# Pure_Keys_aec-pcb4-inprogress.net
KiCad netlist of a schematic drawn in EAGLE
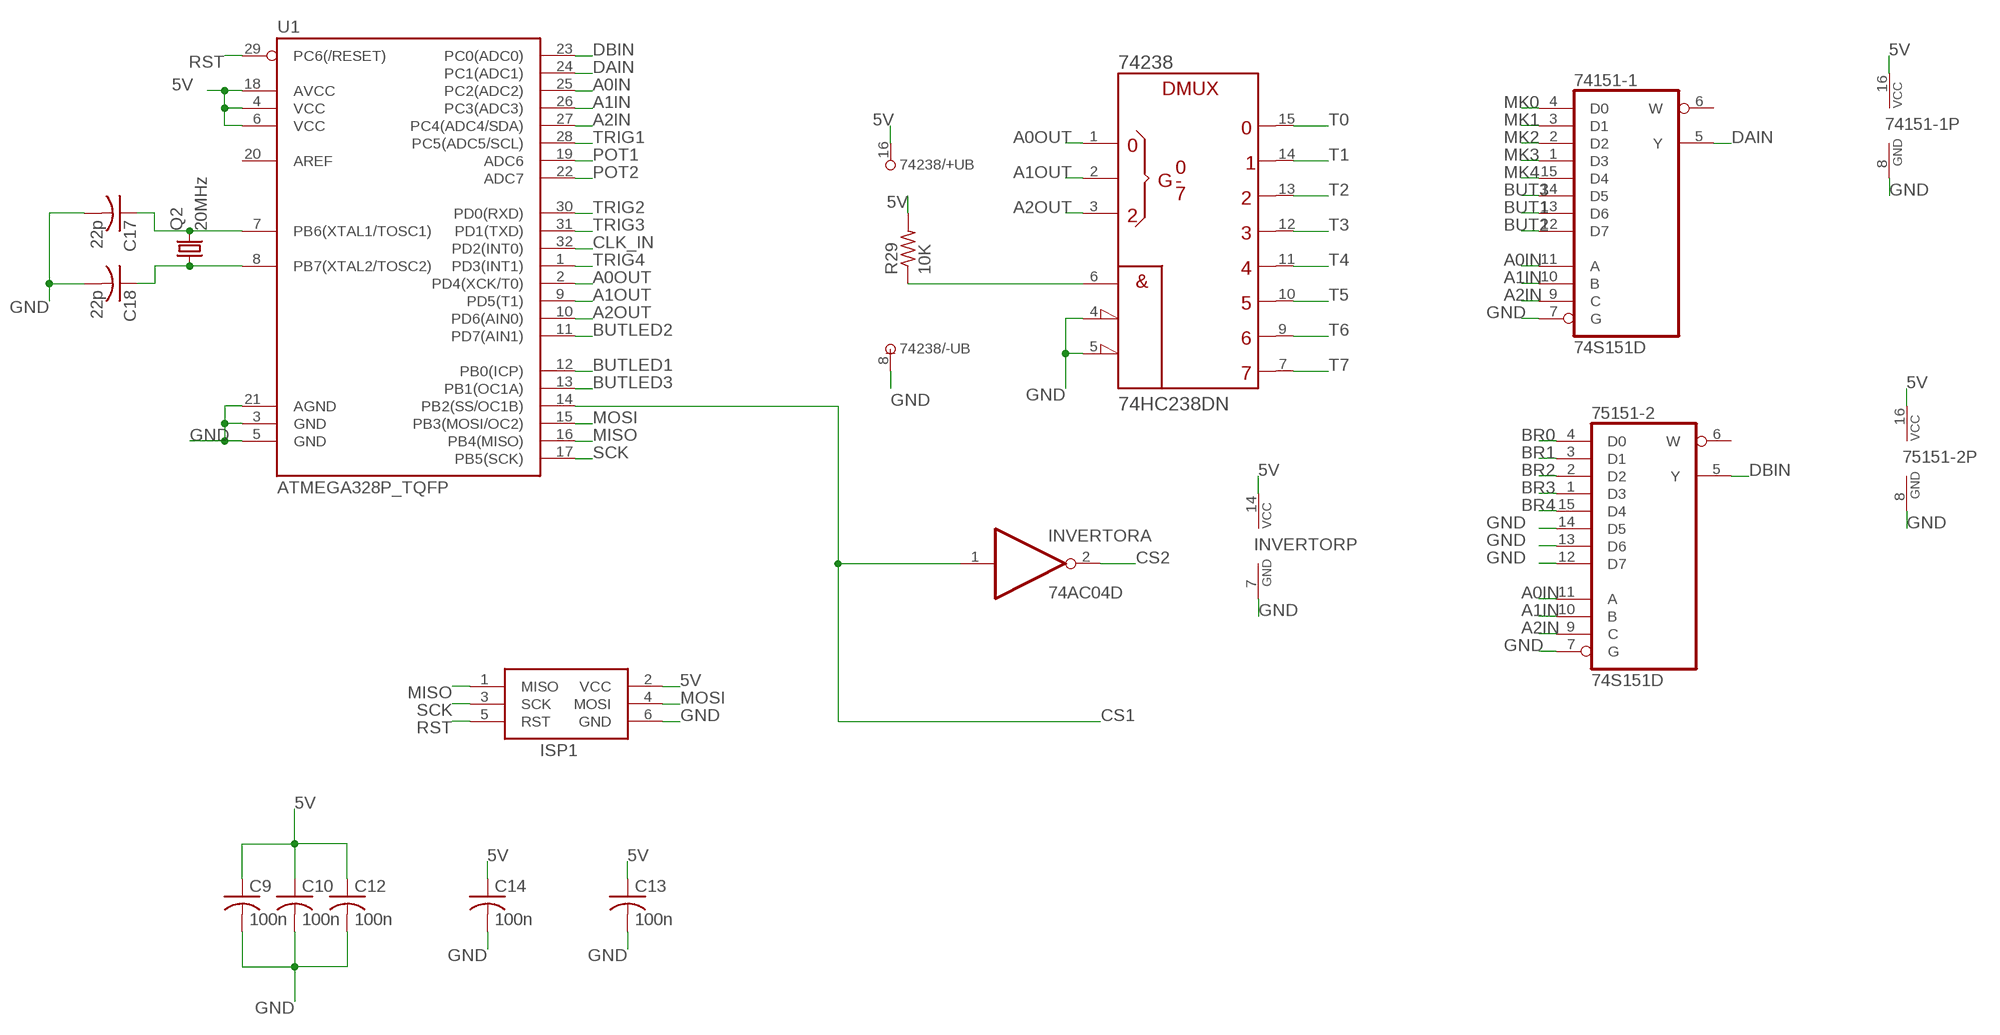
[diagram p0: schematic, sheet 1]
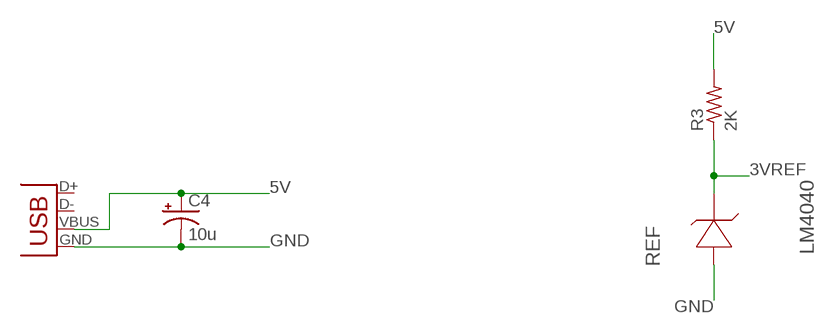
[diagram p1: schematic, sheet 2]
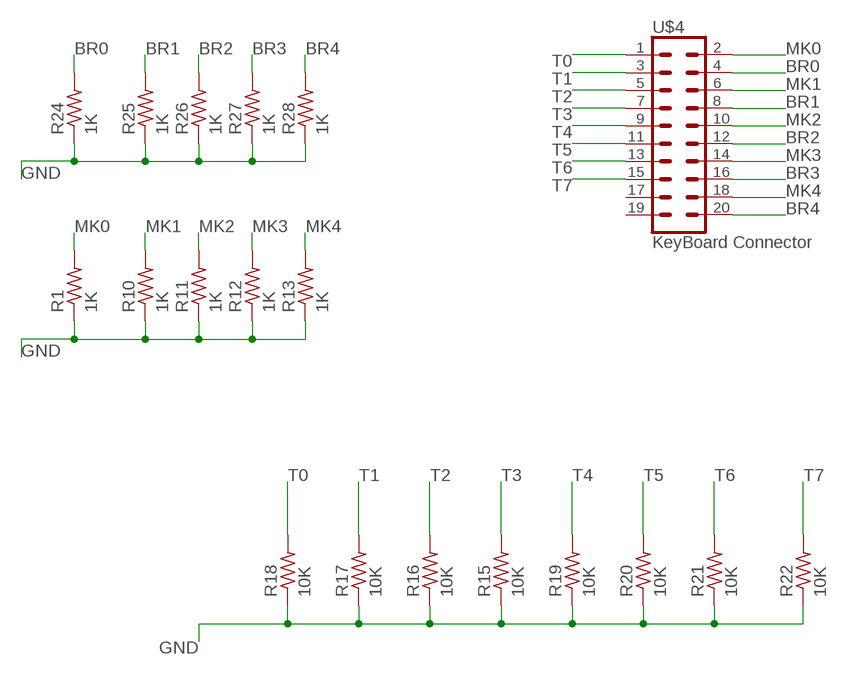
[diagram p2: schematic, sheet 3]
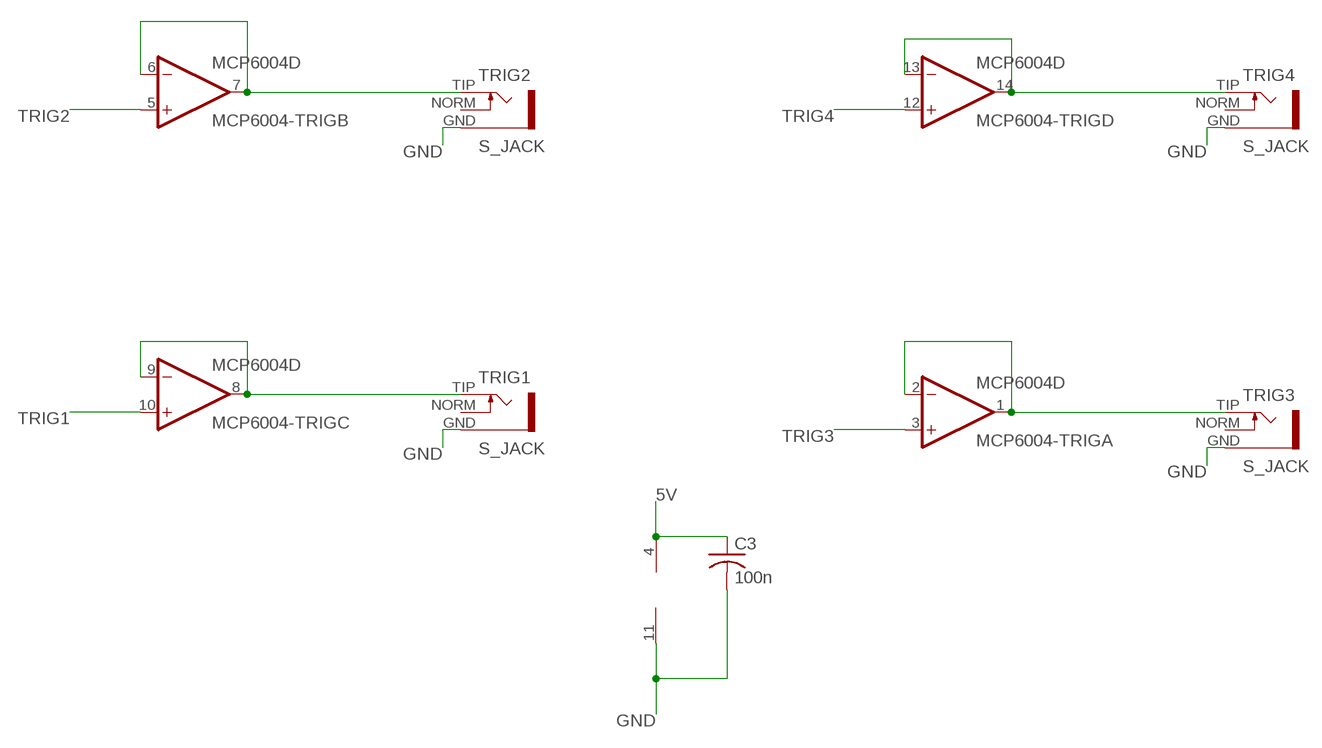
[diagram p3: schematic, sheet 4]
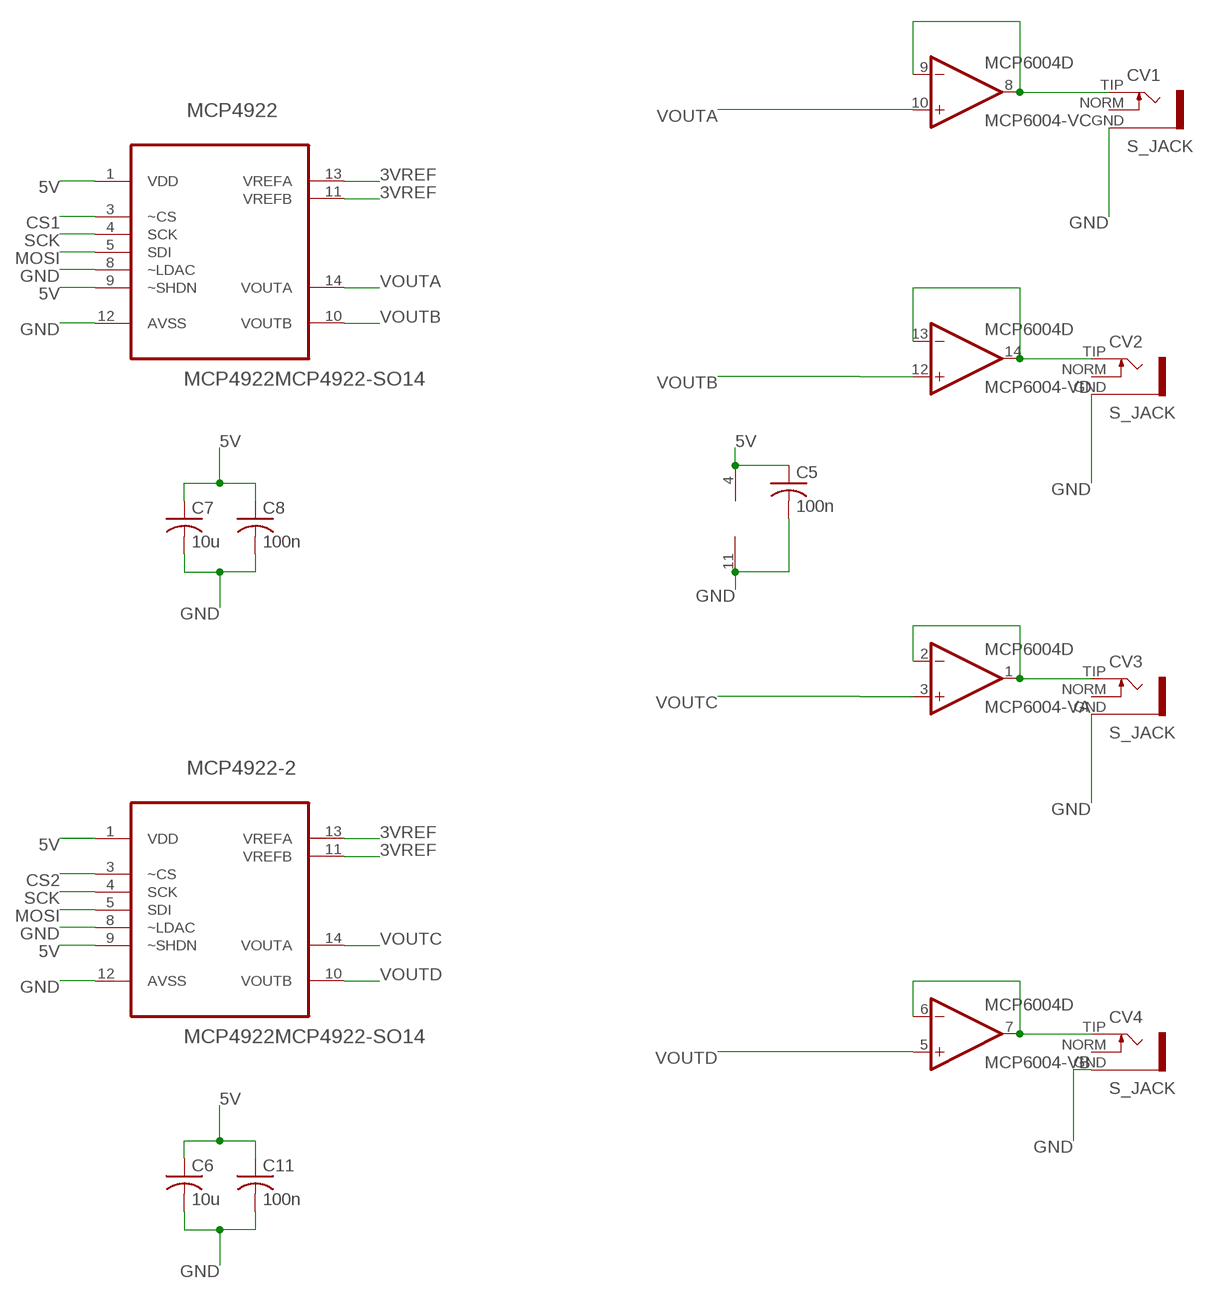
[diagram p4: schematic, sheet 5]
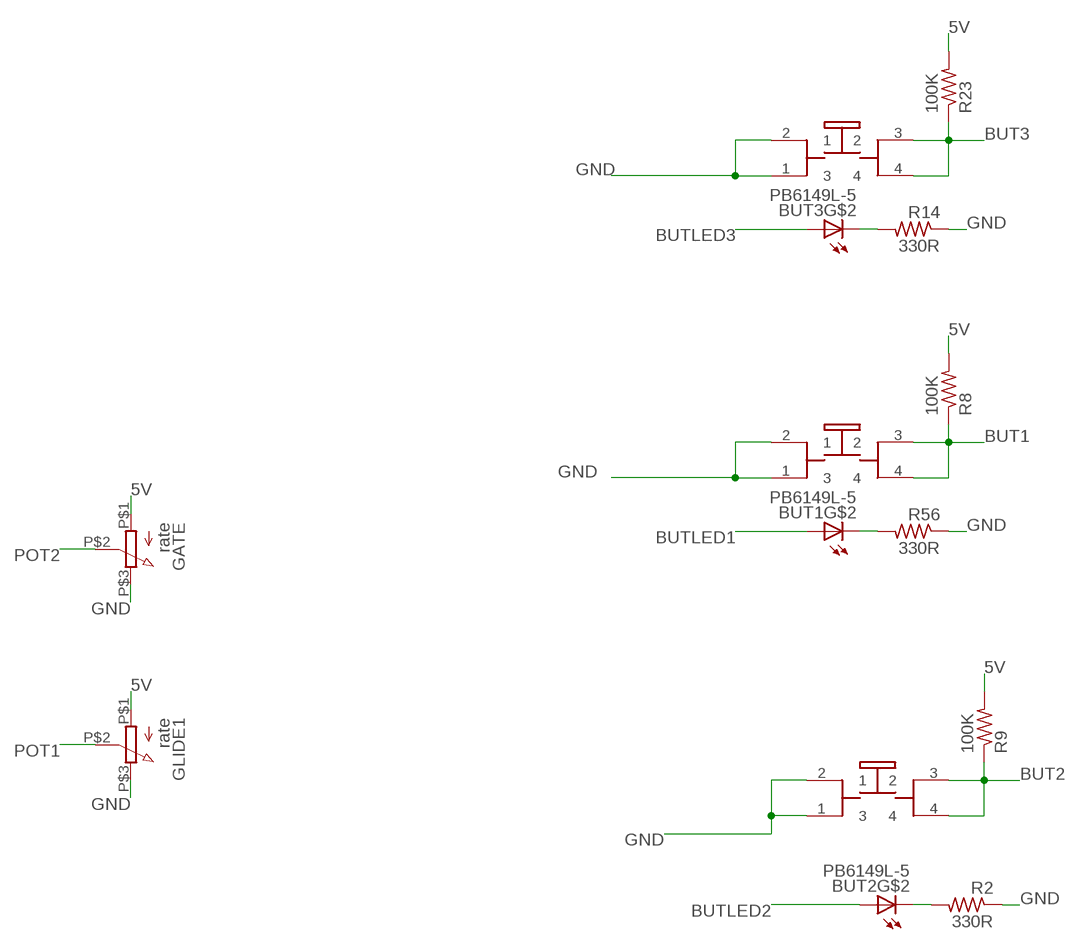
[diagram p5: schematic, sheet 6]
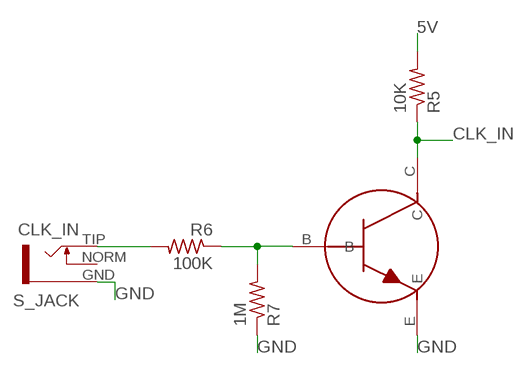
[diagram p6: schematic, sheet 7]

(export (version "E")
  (design (tool "Eeschema 10.0.6"))
  (components
    (comp (ref "CLK_IN")
      (value "S_JACK")
      (footprint "eagle-import:S_JACK")
      (libsource (lib "eagle-import") (part "S_JACK"))
    )
    (comp (ref "CLOCK")
      (value "2N3904")
      (footprint "eagle-import:TRANSISTOR_SINGLE_N-TYPE")
      (fields (field (name "RS-PART") "725-8616 "))
      (libsource (lib "eagle-import") (part "TRANSISTOR_MMBT3904"))
    )
    (comp (ref "R5")
      (value "10K")
      (footprint "eagle-import:R0805")
      (libsource (lib "eagle-import") (part "R-US_R0805"))
    )
    (comp (ref "R6")
      (value "100K")
      (footprint "eagle-import:R0805")
      (libsource (lib "eagle-import") (part "R-US_R0805"))
    )
    (comp (ref "R7")
      (value "1M")
      (footprint "eagle-import:R0805")
      (libsource (lib "eagle-import") (part "R-US_R0805"))
    )
    (comp (ref "74151-1")
      (value "74S151D")
      (footprint "eagle-import:SO16")
      (fields (field (name "RS-PART") "436-7436"))
      (libsource (lib "eagle-import") (part "74151DS"))
    )
    (comp (ref "74238")
      (value "74HC238DN")
      (footprint "eagle-import:SO16")
      (fields (field (name "RS-PART") "483-6487 (10off)"))
      (libsource (lib "eagle-import") (part "74HC238DN"))
    )
    (comp (ref "75151-2")
      (value "74S151D")
      (footprint "eagle-import:SO16")
      (fields (field (name "RS-PART") "436-7436"))
      (libsource (lib "eagle-import") (part "74151DS"))
    )
    (comp (ref "C9")
      (value "100n")
      (footprint "eagle-import:C0805K")
      (libsource (lib "eagle-import") (part "C-USC0805K"))
    )
    (comp (ref "C10")
      (value "100n")
      (footprint "eagle-import:C0805K")
      (libsource (lib "eagle-import") (part "C-USC0805K"))
    )
    (comp (ref "C12")
      (value "100n")
      (footprint "eagle-import:C0805K")
      (libsource (lib "eagle-import") (part "C-USC0805K"))
    )
    (comp (ref "C13")
      (value "100n")
      (footprint "eagle-import:C0805K")
      (libsource (lib "eagle-import") (part "C-USC0805K"))
    )
    (comp (ref "C14")
      (value "100n")
      (footprint "eagle-import:C0805K")
      (libsource (lib "eagle-import") (part "C-USC0805K"))
    )
    (comp (ref "C17")
      (value "22p")
      (footprint "eagle-import:C0805K")
      (libsource (lib "eagle-import") (part "C-USC0805K"))
    )
    (comp (ref "C18")
      (value "22p")
      (footprint "eagle-import:C0805K")
      (libsource (lib "eagle-import") (part "C-USC0805K"))
    )
    (comp (ref "INVERTOR")
      (value "74AC04D")
      (footprint "eagle-import:SO14")
      (fields (field (name "RS-PART") "171-3461 (50 off)"))
      (libsource (lib "eagle-import") (part "7404DAC"))
    )
    (comp (ref "ISP1")
      (value "AVRISP-6")
      (footprint "eagle-import:AVRISP")
      (libsource (lib "eagle-import") (part "AVRISP-6"))
    )
    (comp (ref "Q2")
      (value "20MHz")
      (footprint "eagle-import:HC49UP")
      (libsource (lib "eagle-import") (part "CRYSTALHC49UP"))
    )
    (comp (ref "R29")
      (value "10K")
      (footprint "eagle-import:R0805")
      (libsource (lib "eagle-import") (part "R-US_R0805"))
    )
    (comp (ref "U1")
      (value "ATMEGA328P_TQFP")
      (footprint "eagle-import:TQFP32-08")
      (fields (field (name "RS-PART") "131-0271"))
      (libsource (lib "eagle-import") (part "ATMEGA328P_TQFP"))
    )
    (comp (ref "C4")
      (value "10u")
      (footprint "eagle-import:153CLV-0505")
      (libsource (lib "eagle-import") (part "CPOL-US153CLV-0505"))
    )
    (comp (ref "JP2")
      (value "USB-B")
      (footprint "eagle-import:USB-B-PTH")
      (libsource (lib "eagle-import") (part "USBPTH"))
    )
    (comp (ref "R3")
      (value "2K")
      (footprint "eagle-import:R0805")
      (libsource (lib "eagle-import") (part "R-US_R0805"))
    )
    (comp (ref "REF")
      (value "LM4040")
      (footprint "eagle-import:SOT95P237X112-3N")
      (fields
        (field (name "MPN") "LM4040A50IDBZT")
        (field (name "MPN_1") "LM4040A30IDBZT")
        (field (name "RS-PART") "809-6343")
      )
      (libsource (lib "eagle-import") (part "LM4040A30IDBZT"))
    )
    (comp (ref "BUT1")
      (value "PB6149L-5")
      (footprint "eagle-import:PB6149L")
      (libsource (lib "eagle-import") (part "PB6149L-5"))
    )
    (comp (ref "BUT2")
      (value "PB6149L-5")
      (footprint "eagle-import:PB6149L")
      (libsource (lib "eagle-import") (part "PB6149L-5"))
    )
    (comp (ref "BUT3")
      (value "PB6149L-5")
      (footprint "eagle-import:PB6149L")
      (libsource (lib "eagle-import") (part "PB6149L-5"))
    )
    (comp (ref "GATE")
      (value "rate")
      (footprint "eagle-import:POT")
      (libsource (lib "eagle-import") (part "9MMPOT"))
    )
    (comp (ref "GLIDE1")
      (value "rate")
      (footprint "eagle-import:POT")
      (libsource (lib "eagle-import") (part "9MMPOT"))
    )
    (comp (ref "R2")
      (value "330R")
      (footprint "eagle-import:R0805")
      (libsource (lib "eagle-import") (part "R-US_R0805"))
    )
    (comp (ref "R8")
      (value "100K")
      (footprint "eagle-import:R0805")
      (libsource (lib "eagle-import") (part "R-US_R0805"))
    )
    (comp (ref "R9")
      (value "100K")
      (footprint "eagle-import:R0805")
      (libsource (lib "eagle-import") (part "R-US_R0805"))
    )
    (comp (ref "R14")
      (value "330R")
      (footprint "eagle-import:R0805")
      (libsource (lib "eagle-import") (part "R-US_R0805"))
    )
    (comp (ref "R23")
      (value "100K")
      (footprint "eagle-import:R0805")
      (libsource (lib "eagle-import") (part "R-US_R0805"))
    )
    (comp (ref "R56")
      (value "330R")
      (footprint "eagle-import:R0805")
      (libsource (lib "eagle-import") (part "R-US_R0805"))
    )
    (comp (ref "C3")
      (value "100n")
      (footprint "eagle-import:C0805K")
      (libsource (lib "eagle-import") (part "C-USC0805K"))
    )
    (comp (ref "MCP6004-TRIG")
      (value "MCP6004D")
      (footprint "eagle-import:SO14")
      (fields (field (name "RS-PART") "628-3481 (10)"))
      (libsource (lib "eagle-import") (part "MCP6004D"))
    )
    (comp (ref "TRIG1")
      (value "S_JACK")
      (footprint "eagle-import:S_JACK")
      (libsource (lib "eagle-import") (part "S_JACK"))
    )
    (comp (ref "TRIG2")
      (value "S_JACK")
      (footprint "eagle-import:S_JACK")
      (libsource (lib "eagle-import") (part "S_JACK"))
    )
    (comp (ref "TRIG3")
      (value "S_JACK")
      (footprint "eagle-import:S_JACK")
      (libsource (lib "eagle-import") (part "S_JACK"))
    )
    (comp (ref "TRIG4")
      (value "S_JACK")
      (footprint "eagle-import:S_JACK")
      (libsource (lib "eagle-import") (part "S_JACK"))
    )
    (comp (ref "R1")
      (value "1K")
      (footprint "eagle-import:R0805")
      (fields (field (name "RS-PART") "223-0427"))
      (libsource (lib "eagle-import") (part "R-US_R0805"))
    )
    (comp (ref "R10")
      (value "1K")
      (footprint "eagle-import:R0805")
      (fields (field (name "RS-PART") "223-0427"))
      (libsource (lib "eagle-import") (part "R-US_R0805"))
    )
    (comp (ref "R11")
      (value "1K")
      (footprint "eagle-import:R0805")
      (fields (field (name "RS-PART") "223-0427"))
      (libsource (lib "eagle-import") (part "R-US_R0805"))
    )
    (comp (ref "R12")
      (value "1K")
      (footprint "eagle-import:R0805")
      (fields (field (name "RS-PART") "223-0427"))
      (libsource (lib "eagle-import") (part "R-US_R0805"))
    )
    (comp (ref "R13")
      (value "1K")
      (footprint "eagle-import:R0805")
      (fields (field (name "RS-PART") "223-0427"))
      (libsource (lib "eagle-import") (part "R-US_R0805"))
    )
    (comp (ref "R15")
      (value "10K")
      (footprint "eagle-import:R0805")
      (libsource (lib "eagle-import") (part "R-US_R0805"))
    )
    (comp (ref "R16")
      (value "10K")
      (footprint "eagle-import:R0805")
      (libsource (lib "eagle-import") (part "R-US_R0805"))
    )
    (comp (ref "R17")
      (value "10K")
      (footprint "eagle-import:R0805")
      (libsource (lib "eagle-import") (part "R-US_R0805"))
    )
    (comp (ref "R18")
      (value "10K")
      (footprint "eagle-import:R0805")
      (libsource (lib "eagle-import") (part "R-US_R0805"))
    )
    (comp (ref "R19")
      (value "10K")
      (footprint "eagle-import:R0805")
      (libsource (lib "eagle-import") (part "R-US_R0805"))
    )
    (comp (ref "R20")
      (value "10K")
      (footprint "eagle-import:R0805")
      (libsource (lib "eagle-import") (part "R-US_R0805"))
    )
    (comp (ref "R21")
      (value "10K")
      (footprint "eagle-import:R0805")
      (libsource (lib "eagle-import") (part "R-US_R0805"))
    )
    (comp (ref "R22")
      (value "10K")
      (footprint "eagle-import:R0805")
      (libsource (lib "eagle-import") (part "R-US_R0805"))
    )
    (comp (ref "R24")
      (value "1K")
      (footprint "eagle-import:R0805")
      (fields (field (name "RS-PART") "223-0427"))
      (libsource (lib "eagle-import") (part "R-US_R0805"))
    )
    (comp (ref "R25")
      (value "1K")
      (footprint "eagle-import:R0805")
      (fields (field (name "RS-PART") "223-0427"))
      (libsource (lib "eagle-import") (part "R-US_R0805"))
    )
    (comp (ref "R26")
      (value "1K")
      (footprint "eagle-import:R0805")
      (fields (field (name "RS-PART") "223-0427"))
      (libsource (lib "eagle-import") (part "R-US_R0805"))
    )
    (comp (ref "R27")
      (value "1K")
      (footprint "eagle-import:R0805")
      (fields (field (name "RS-PART") "223-0427"))
      (libsource (lib "eagle-import") (part "R-US_R0805"))
    )
    (comp (ref "R28")
      (value "1K")
      (footprint "eagle-import:R0805")
      (fields (field (name "RS-PART") "223-0427"))
      (libsource (lib "eagle-import") (part "R-US_R0805"))
    )
    (comp (ref "U$4")
      (value "KeyBoard Connector")
      (footprint "eagle-import:2X10")
      (fields (field (name "RS-PART") "669-5364"))
      (libsource (lib "eagle-import") (part "CONN_10X2"))
    )
    (comp (ref "C5")
      (value "100n")
      (footprint "eagle-import:C0805K")
      (libsource (lib "eagle-import") (part "C-USC0805K"))
    )
    (comp (ref "C6")
      (value "10u")
      (footprint "eagle-import:C0805K")
      (libsource (lib "eagle-import") (part "C-USC0805K"))
    )
    (comp (ref "C7")
      (value "10u")
      (footprint "eagle-import:C0805K")
      (libsource (lib "eagle-import") (part "C-USC0805K"))
    )
    (comp (ref "C8")
      (value "100n")
      (footprint "eagle-import:C0805K")
      (libsource (lib "eagle-import") (part "C-USC0805K"))
    )
    (comp (ref "C11")
      (value "100n")
      (footprint "eagle-import:C0805K")
      (libsource (lib "eagle-import") (part "C-USC0805K"))
    )
    (comp (ref "CV1")
      (value "S_JACK")
      (footprint "eagle-import:S_JACK")
      (libsource (lib "eagle-import") (part "S_JACK"))
    )
    (comp (ref "CV2")
      (value "S_JACK")
      (footprint "eagle-import:S_JACK")
      (libsource (lib "eagle-import") (part "S_JACK"))
    )
    (comp (ref "CV3")
      (value "S_JACK")
      (footprint "eagle-import:S_JACK")
      (libsource (lib "eagle-import") (part "S_JACK"))
    )
    (comp (ref "CV4")
      (value "S_JACK")
      (footprint "eagle-import:S_JACK")
      (libsource (lib "eagle-import") (part "S_JACK"))
    )
    (comp (ref "MCP4922")
      (value "MCP4922MCP4922-SO14")
      (footprint "eagle-import:SO14")
      (fields (field (name "RS-PART") "402-910 "))
      (libsource (lib "eagle-import") (part "MCP4922MCP4922-SO14"))
    )
    (comp (ref "MCP4922-2")
      (value "MCP4922MCP4922-SO14")
      (footprint "eagle-import:SO14")
      (libsource (lib "eagle-import") (part "MCP4922MCP4922-SO14"))
    )
    (comp (ref "MCP6004-V")
      (value "MCP6004D")
      (footprint "eagle-import:SO14")
      (fields (field (name "RS-PART") "628-3481 (10)"))
      (libsource (lib "eagle-import") (part "MCP6004D"))
    )
  )
  (nets
    (net (code "1") (name "3VREF") (class "Default")
      (node (ref "MCP4922") (pin "11") (pinfunction "VREFB_11") (pintype "bidirectional"))
      (node (ref "MCP4922") (pin "13") (pinfunction "VREFA_13") (pintype "input"))
      (node (ref "MCP4922-2") (pin "11") (pinfunction "VREFB_11") (pintype "bidirectional"))
      (node (ref "MCP4922-2") (pin "13") (pinfunction "VREFA_13") (pintype "input"))
      (node (ref "R3") (pin "1") (pinfunction "1_1") (pintype "passive"))
      (node (ref "REF") (pin "1") (pinfunction "CATHODE_1") (pintype "output"))
    )
    (net (code "2") (name "5V") (class "Default")
      (node (ref "74151-1") (pin "16") (pinfunction "VCC_16") (pintype "power_in"))
      (node (ref "74238") (pin "16") (pinfunction "+UB_16") (pintype "power_in"))
      (node (ref "75151-2") (pin "16") (pinfunction "VCC_16") (pintype "power_in"))
      (node (ref "C10") (pin "1") (pinfunction "1_1") (pintype "passive"))
      (node (ref "C11") (pin "1") (pinfunction "1_1") (pintype "passive"))
      (node (ref "C12") (pin "1") (pinfunction "1_1") (pintype "passive"))
      (node (ref "C13") (pin "1") (pinfunction "1_1") (pintype "passive"))
      (node (ref "C14") (pin "1") (pinfunction "1_1") (pintype "passive"))
      (node (ref "C3") (pin "1") (pinfunction "1_1") (pintype "passive"))
      (node (ref "C4") (pin "+") (pinfunction "+_+") (pintype "passive"))
      (node (ref "C5") (pin "1") (pinfunction "1_1") (pintype "passive"))
      (node (ref "C6") (pin "1") (pinfunction "1_1") (pintype "passive"))
      (node (ref "C7") (pin "1") (pinfunction "1_1") (pintype "passive"))
      (node (ref "C8") (pin "1") (pinfunction "1_1") (pintype "passive"))
      (node (ref "C9") (pin "1") (pinfunction "1_1") (pintype "passive"))
      (node (ref "GATE") (pin "P$1") (pinfunction "1_P$1") (pintype "passive"))
      (node (ref "GLIDE1") (pin "P$1") (pinfunction "1_P$1") (pintype "passive"))
      (node (ref "INVERTOR") (pin "14") (pinfunction "VCC_14") (pintype "power_in"))
      (node (ref "ISP1") (pin "2") (pinfunction "VCC_2") (pintype "power_in"))
      (node (ref "JP2") (pin "VBUS") (pinfunction "VBUS_VBUS") (pintype "bidirectional"))
      (node (ref "MCP4922") (pin "1") (pinfunction "VDD_1") (pintype "power_in"))
      (node (ref "MCP4922") (pin "9") (pinfunction "~{SHDN}_9") (pintype "bidirectional"))
      (node (ref "MCP4922-2") (pin "1") (pinfunction "VDD_1") (pintype "power_in"))
      (node (ref "MCP4922-2") (pin "9") (pinfunction "~{SHDN}_9") (pintype "bidirectional"))
      (node (ref "MCP6004-TRIG") (pin "4") (pinfunction "V+_4") (pintype "power_in"))
      (node (ref "MCP6004-V") (pin "4") (pinfunction "V+_4") (pintype "power_in"))
      (node (ref "R23") (pin "2") (pinfunction "2_2") (pintype "passive"))
      (node (ref "R29") (pin "2") (pinfunction "2_2") (pintype "passive"))
      (node (ref "R3") (pin "2") (pinfunction "2_2") (pintype "passive"))
      (node (ref "R5") (pin "2") (pinfunction "2_2") (pintype "passive"))
      (node (ref "R8") (pin "2") (pinfunction "2_2") (pintype "passive"))
      (node (ref "R9") (pin "2") (pinfunction "2_2") (pintype "passive"))
      (node (ref "U1") (pin "18") (pinfunction "AVCC_18") (pintype "bidirectional"))
      (node (ref "U1") (pin "4") (pinfunction "VCC_4") (pintype "bidirectional"))
      (node (ref "U1") (pin "6") (pinfunction "VCC_6") (pintype "bidirectional"))
    )
    (net (code "3") (name "A0IN") (class "Default")
      (node (ref "74151-1") (pin "11") (pinfunction "A_11") (pintype "input"))
      (node (ref "75151-2") (pin "11") (pinfunction "A_11") (pintype "input"))
      (node (ref "U1") (pin "25") (pinfunction "PC2(ADC2)_25") (pintype "bidirectional"))
    )
    (net (code "4") (name "A0OUT") (class "Default")
      (node (ref "74238") (pin "1") (pinfunction "A_1") (pintype "input"))
      (node (ref "U1") (pin "2") (pinfunction "PD4(XCK/T0)_2") (pintype "bidirectional"))
    )
    (net (code "5") (name "A1IN") (class "Default")
      (node (ref "74151-1") (pin "10") (pinfunction "B_10") (pintype "input"))
      (node (ref "75151-2") (pin "10") (pinfunction "B_10") (pintype "input"))
      (node (ref "U1") (pin "26") (pinfunction "PC3(ADC3)_26") (pintype "bidirectional"))
    )
    (net (code "6") (name "A1OUT") (class "Default")
      (node (ref "74238") (pin "2") (pinfunction "B_2") (pintype "input"))
      (node (ref "U1") (pin "9") (pinfunction "PD5(T1)_9") (pintype "bidirectional"))
    )
    (net (code "7") (name "A2IN") (class "Default")
      (node (ref "74151-1") (pin "9") (pinfunction "C_9") (pintype "input"))
      (node (ref "75151-2") (pin "9") (pinfunction "C_9") (pintype "input"))
      (node (ref "U1") (pin "27") (pinfunction "PC4(ADC4/SDA)_27") (pintype "bidirectional"))
    )
    (net (code "8") (name "A2OUT") (class "Default")
      (node (ref "74238") (pin "3") (pinfunction "C_3") (pintype "input"))
      (node (ref "U1") (pin "10") (pinfunction "PD6(AIN0)_10") (pintype "bidirectional"))
    )
    (net (code "9") (name "BR0") (class "Default")
      (node (ref "75151-2") (pin "4") (pinfunction "D0_4") (pintype "input"))
      (node (ref "R24") (pin "2") (pinfunction "2_2") (pintype "passive"))
      (node (ref "U$4") (pin "4") (pinfunction "4_4") (pintype "passive"))
    )
    (net (code "10") (name "BR1") (class "Default")
      (node (ref "75151-2") (pin "3") (pinfunction "D1_3") (pintype "input"))
      (node (ref "R25") (pin "2") (pinfunction "2_2") (pintype "passive"))
      (node (ref "U$4") (pin "8") (pinfunction "8_8") (pintype "passive"))
    )
    (net (code "11") (name "BR2") (class "Default")
      (node (ref "75151-2") (pin "2") (pinfunction "D2_2") (pintype "input"))
      (node (ref "R26") (pin "2") (pinfunction "2_2") (pintype "passive"))
      (node (ref "U$4") (pin "12") (pinfunction "12_12") (pintype "passive"))
    )
    (net (code "12") (name "BR3") (class "Default")
      (node (ref "75151-2") (pin "1") (pinfunction "D3_1") (pintype "input"))
      (node (ref "R27") (pin "2") (pinfunction "2_2") (pintype "passive"))
      (node (ref "U$4") (pin "16") (pinfunction "16_16") (pintype "passive"))
    )
    (net (code "13") (name "BR4") (class "Default")
      (node (ref "75151-2") (pin "15") (pinfunction "D4_15") (pintype "input"))
      (node (ref "R28") (pin "2") (pinfunction "2_2") (pintype "passive"))
      (node (ref "U$4") (pin "20") (pinfunction "20_20") (pintype "passive"))
    )
    (net (code "14") (name "BUT1") (class "Default")
      (node (ref "74151-1") (pin "13") (pinfunction "D6_13") (pintype "input"))
      (node (ref "BUT1") (pin "3") (pinfunction "2_3") (pintype "bidirectional"))
      (node (ref "BUT1") (pin "4") (pinfunction "4_4") (pintype "bidirectional"))
      (node (ref "R8") (pin "1") (pinfunction "1_1") (pintype "passive"))
    )
    (net (code "15") (name "BUT2") (class "Default")
      (node (ref "74151-1") (pin "12") (pinfunction "D7_12") (pintype "input"))
      (node (ref "BUT2") (pin "3") (pinfunction "2_3") (pintype "bidirectional"))
      (node (ref "BUT2") (pin "4") (pinfunction "4_4") (pintype "bidirectional"))
      (node (ref "R9") (pin "1") (pinfunction "1_1") (pintype "passive"))
    )
    (net (code "16") (name "BUT3") (class "Default")
      (node (ref "74151-1") (pin "14") (pinfunction "D5_14") (pintype "input"))
      (node (ref "BUT3") (pin "3") (pinfunction "2_3") (pintype "bidirectional"))
      (node (ref "BUT3") (pin "4") (pinfunction "4_4") (pintype "bidirectional"))
      (node (ref "R23") (pin "1") (pinfunction "1_1") (pintype "passive"))
    )
    (net (code "17") (name "BUTLED1") (class "Default")
      (node (ref "BUT1") (pin "A") (pinfunction "A_A") (pintype "passive"))
      (node (ref "U1") (pin "12") (pinfunction "PB0(ICP)_12") (pintype "bidirectional"))
    )
    (net (code "18") (name "BUTLED2") (class "Default")
      (node (ref "BUT2") (pin "A") (pinfunction "A_A") (pintype "passive"))
      (node (ref "U1") (pin "11") (pinfunction "PD7(AIN1)_11") (pintype "bidirectional"))
    )
    (net (code "19") (name "BUTLED3") (class "Default")
      (node (ref "BUT3") (pin "A") (pinfunction "A_A") (pintype "passive"))
      (node (ref "U1") (pin "13") (pinfunction "PB1(OC1A)_13") (pintype "bidirectional"))
    )
    (net (code "20") (name "CLK_IN") (class "Default")
      (node (ref "CLOCK") (pin "C") (pinfunction "C_C") (pintype "bidirectional"))
      (node (ref "R5") (pin "1") (pinfunction "1_1") (pintype "passive"))
      (node (ref "U1") (pin "32") (pinfunction "PD2(INT0)_32") (pintype "bidirectional"))
    )
    (net (code "21") (name "CS1") (class "Default")
      (node (ref "INVERTOR") (pin "1") (pinfunction "I_1") (pintype "input"))
      (node (ref "MCP4922") (pin "3") (pinfunction "~{CS}_3") (pintype "input"))
      (node (ref "U1") (pin "14") (pinfunction "PB2(SS/OC1B)_14") (pintype "bidirectional"))
    )
    (net (code "22") (name "CS2") (class "Default")
      (node (ref "INVERTOR") (pin "2") (pinfunction "O_2") (pintype "output"))
      (node (ref "MCP4922-2") (pin "3") (pinfunction "~{CS}_3") (pintype "input"))
    )
    (net (code "23") (name "DAIN") (class "Default")
      (node (ref "74151-1") (pin "5") (pinfunction "Y_5") (pintype "output"))
      (node (ref "U1") (pin "24") (pinfunction "PC1(ADC1)_24") (pintype "bidirectional"))
    )
    (net (code "24") (name "DBIN") (class "Default")
      (node (ref "75151-2") (pin "5") (pinfunction "Y_5") (pintype "output"))
      (node (ref "U1") (pin "23") (pinfunction "PC0(ADC0)_23") (pintype "bidirectional"))
    )
    (net (code "25") (name "GND") (class "Default")
      (node (ref "74151-1") (pin "7") (pinfunction "G_7") (pintype "input"))
      (node (ref "74151-1") (pin "8") (pinfunction "GND_8") (pintype "power_in"))
      (node (ref "74238") (pin "4") (pinfunction "~{G2A}_4") (pintype "input"))
      (node (ref "74238") (pin "5") (pinfunction "~{G2B}_5") (pintype "input"))
      (node (ref "74238") (pin "8") (pinfunction "-UB_8") (pintype "power_in"))
      (node (ref "75151-2") (pin "12") (pinfunction "D7_12") (pintype "input"))
      (node (ref "75151-2") (pin "13") (pinfunction "D6_13") (pintype "input"))
      (node (ref "75151-2") (pin "14") (pinfunction "D5_14") (pintype "input"))
      (node (ref "75151-2") (pin "7") (pinfunction "G_7") (pintype "input"))
      (node (ref "75151-2") (pin "8") (pinfunction "GND_8") (pintype "power_in"))
      (node (ref "BUT1") (pin "1") (pinfunction "3_1") (pintype "bidirectional"))
      (node (ref "BUT1") (pin "2") (pinfunction "1_2") (pintype "bidirectional"))
      (node (ref "BUT2") (pin "1") (pinfunction "3_1") (pintype "bidirectional"))
      (node (ref "BUT2") (pin "2") (pinfunction "1_2") (pintype "bidirectional"))
      (node (ref "BUT3") (pin "1") (pinfunction "3_1") (pintype "bidirectional"))
      (node (ref "BUT3") (pin "2") (pinfunction "1_2") (pintype "bidirectional"))
      (node (ref "C10") (pin "2") (pinfunction "2_2") (pintype "passive"))
      (node (ref "C11") (pin "2") (pinfunction "2_2") (pintype "passive"))
      (node (ref "C12") (pin "2") (pinfunction "2_2") (pintype "passive"))
      (node (ref "C13") (pin "2") (pinfunction "2_2") (pintype "passive"))
      (node (ref "C14") (pin "2") (pinfunction "2_2") (pintype "passive"))
      (node (ref "C17") (pin "2") (pinfunction "2_2") (pintype "passive"))
      (node (ref "C18") (pin "2") (pinfunction "2_2") (pintype "passive"))
      (node (ref "C3") (pin "2") (pinfunction "2_2") (pintype "passive"))
      (node (ref "C4") (pin "-") (pinfunction "-_-") (pintype "passive"))
      (node (ref "C5") (pin "2") (pinfunction "2_2") (pintype "passive"))
      (node (ref "C6") (pin "2") (pinfunction "2_2") (pintype "passive"))
      (node (ref "C7") (pin "2") (pinfunction "2_2") (pintype "passive"))
      (node (ref "C8") (pin "2") (pinfunction "2_2") (pintype "passive"))
      (node (ref "C9") (pin "2") (pinfunction "2_2") (pintype "passive"))
      (node (ref "CLK_IN") (pin "GND") (pinfunction "GND_GND") (pintype "passive"))
      (node (ref "CLOCK") (pin "E") (pinfunction "E_E") (pintype "bidirectional"))
      (node (ref "CV1") (pin "GND") (pinfunction "GND_GND") (pintype "passive"))
      (node (ref "CV2") (pin "GND") (pinfunction "GND_GND") (pintype "passive"))
      (node (ref "CV3") (pin "GND") (pinfunction "GND_GND") (pintype "passive"))
      (node (ref "CV4") (pin "GND") (pinfunction "GND_GND") (pintype "passive"))
      (node (ref "GATE") (pin "P$3") (pinfunction "3_P$3") (pintype "passive"))
      (node (ref "GLIDE1") (pin "P$3") (pinfunction "3_P$3") (pintype "passive"))
      (node (ref "INVERTOR") (pin "7") (pinfunction "GND_7") (pintype "power_in"))
      (node (ref "ISP1") (pin "6") (pinfunction "GND_6") (pintype "power_in"))
      (node (ref "JP2") (pin "GND") (pinfunction "GND_GND") (pintype "bidirectional"))
      (node (ref "MCP4922") (pin "12") (pinfunction "AVSS_12") (pintype "passive"))
      (node (ref "MCP4922") (pin "8") (pinfunction "~{LDAC}_8") (pintype "input"))
      (node (ref "MCP4922-2") (pin "12") (pinfunction "AVSS_12") (pintype "passive"))
      (node (ref "MCP4922-2") (pin "8") (pinfunction "~{LDAC}_8") (pintype "input"))
      (node (ref "MCP6004-TRIG") (pin "11") (pinfunction "V-_11") (pintype "power_in"))
      (node (ref "MCP6004-V") (pin "11") (pinfunction "V-_11") (pintype "power_in"))
      (node (ref "R1") (pin "1") (pinfunction "1_1") (pintype "passive"))
      (node (ref "R10") (pin "1") (pinfunction "1_1") (pintype "passive"))
      (node (ref "R11") (pin "1") (pinfunction "1_1") (pintype "passive"))
      (node (ref "R12") (pin "1") (pinfunction "1_1") (pintype "passive"))
      (node (ref "R13") (pin "1") (pinfunction "1_1") (pintype "passive"))
      (node (ref "R14") (pin "1") (pinfunction "1_1") (pintype "passive"))
      (node (ref "R15") (pin "1") (pinfunction "1_1") (pintype "passive"))
      (node (ref "R16") (pin "1") (pinfunction "1_1") (pintype "passive"))
      (node (ref "R17") (pin "1") (pinfunction "1_1") (pintype "passive"))
      (node (ref "R18") (pin "1") (pinfunction "1_1") (pintype "passive"))
      (node (ref "R19") (pin "1") (pinfunction "1_1") (pintype "passive"))
      (node (ref "R2") (pin "1") (pinfunction "1_1") (pintype "passive"))
      (node (ref "R20") (pin "1") (pinfunction "1_1") (pintype "passive"))
      (node (ref "R21") (pin "1") (pinfunction "1_1") (pintype "passive"))
      (node (ref "R22") (pin "1") (pinfunction "1_1") (pintype "passive"))
      (node (ref "R24") (pin "1") (pinfunction "1_1") (pintype "passive"))
      (node (ref "R25") (pin "1") (pinfunction "1_1") (pintype "passive"))
      (node (ref "R26") (pin "1") (pinfunction "1_1") (pintype "passive"))
      (node (ref "R27") (pin "1") (pinfunction "1_1") (pintype "passive"))
      (node (ref "R28") (pin "1") (pinfunction "1_1") (pintype "passive"))
      (node (ref "R56") (pin "1") (pinfunction "1_1") (pintype "passive"))
      (node (ref "R7") (pin "1") (pinfunction "1_1") (pintype "passive"))
      (node (ref "REF") (pin "2") (pinfunction "ANODE_2") (pintype "input"))
      (node (ref "TRIG1") (pin "GND") (pinfunction "GND_GND") (pintype "passive"))
      (node (ref "TRIG2") (pin "GND") (pinfunction "GND_GND") (pintype "passive"))
      (node (ref "TRIG3") (pin "GND") (pinfunction "GND_GND") (pintype "passive"))
      (node (ref "TRIG4") (pin "GND") (pinfunction "GND_GND") (pintype "passive"))
      (node (ref "U1") (pin "21") (pinfunction "AGND_21") (pintype "bidirectional"))
      (node (ref "U1") (pin "3") (pinfunction "GND_3") (pintype "bidirectional"))
      (node (ref "U1") (pin "5") (pinfunction "GND_5") (pintype "bidirectional"))
    )
    (net (code "26") (name "MISO") (class "Default")
      (node (ref "ISP1") (pin "1") (pinfunction "MISO_1") (pintype "input"))
      (node (ref "U1") (pin "16") (pinfunction "PB4(MISO)_16") (pintype "bidirectional"))
    )
    (net (code "27") (name "MK0") (class "Default")
      (node (ref "74151-1") (pin "4") (pinfunction "D0_4") (pintype "input"))
      (node (ref "R1") (pin "2") (pinfunction "2_2") (pintype "passive"))
      (node (ref "U$4") (pin "2") (pinfunction "2_2") (pintype "passive"))
    )
    (net (code "28") (name "MK1") (class "Default")
      (node (ref "74151-1") (pin "3") (pinfunction "D1_3") (pintype "input"))
      (node (ref "R10") (pin "2") (pinfunction "2_2") (pintype "passive"))
      (node (ref "U$4") (pin "6") (pinfunction "6_6") (pintype "passive"))
    )
    (net (code "29") (name "MK2") (class "Default")
      (node (ref "74151-1") (pin "2") (pinfunction "D2_2") (pintype "input"))
      (node (ref "R11") (pin "2") (pinfunction "2_2") (pintype "passive"))
      (node (ref "U$4") (pin "10") (pinfunction "10_10") (pintype "passive"))
    )
    (net (code "30") (name "MK3") (class "Default")
      (node (ref "74151-1") (pin "1") (pinfunction "D3_1") (pintype "input"))
      (node (ref "R12") (pin "2") (pinfunction "2_2") (pintype "passive"))
      (node (ref "U$4") (pin "14") (pinfunction "14_14") (pintype "passive"))
    )
    (net (code "31") (name "MK4") (class "Default")
      (node (ref "74151-1") (pin "15") (pinfunction "D4_15") (pintype "input"))
      (node (ref "R13") (pin "2") (pinfunction "2_2") (pintype "passive"))
      (node (ref "U$4") (pin "18") (pinfunction "18_18") (pintype "passive"))
    )
    (net (code "32") (name "MOSI") (class "Default")
      (node (ref "ISP1") (pin "4") (pinfunction "MOSI_4") (pintype "output"))
      (node (ref "MCP4922") (pin "5") (pinfunction "SDI_5") (pintype "input"))
      (node (ref "MCP4922-2") (pin "5") (pinfunction "SDI_5") (pintype "input"))
      (node (ref "U1") (pin "15") (pinfunction "PB3(MOSI/OC2)_15") (pintype "bidirectional"))
    )
    (net (code "33") (name "Net-(74238C-G1)") (class "Default")
      (node (ref "74238") (pin "6") (pinfunction "G1_6") (pintype "input"))
      (node (ref "R29") (pin "1") (pinfunction "1_1") (pintype "passive"))
    )
    (net (code "34") (name "Net-(BUT1B-C)") (class "Default")
      (node (ref "BUT1") (pin "K") (pinfunction "C_K") (pintype "passive"))
      (node (ref "R56") (pin "2") (pinfunction "2_2") (pintype "passive"))
    )
    (net (code "35") (name "Net-(BUT2B-C)") (class "Default")
      (node (ref "BUT2") (pin "K") (pinfunction "C_K") (pintype "passive"))
      (node (ref "R2") (pin "2") (pinfunction "2_2") (pintype "passive"))
    )
    (net (code "36") (name "Net-(BUT3B-C)") (class "Default")
      (node (ref "BUT3") (pin "K") (pinfunction "C_K") (pintype "passive"))
      (node (ref "R14") (pin "2") (pinfunction "2_2") (pintype "passive"))
    )
    (net (code "37") (name "Net-(CLK_IN-PadTIP)") (class "Default")
      (node (ref "CLK_IN") (pin "TIP") (pinfunction "TIP_TIP") (pintype "passive"))
      (node (ref "R6") (pin "2") (pinfunction "2_2") (pintype "passive"))
    )
    (net (code "38") (name "Net-(CLOCK-PadB)") (class "Default")
      (node (ref "CLOCK") (pin "B") (pinfunction "B_B") (pintype "bidirectional"))
      (node (ref "R6") (pin "1") (pinfunction "1_1") (pintype "passive"))
      (node (ref "R7") (pin "2") (pinfunction "2_2") (pintype "passive"))
    )
    (net (code "39") (name "Net-(MCP6004-TRIGA--IN)") (class "Default")
      (node (ref "MCP6004-TRIG") (pin "1") (pinfunction "OUT_1") (pintype "output"))
      (node (ref "MCP6004-TRIG") (pin "2") (pinfunction "-IN_2") (pintype "input"))
      (node (ref "TRIG3") (pin "TIP") (pinfunction "TIP_TIP") (pintype "passive"))
    )
    (net (code "40") (name "Net-(MCP6004-TRIGB--IN)") (class "Default")
      (node (ref "MCP6004-TRIG") (pin "6") (pinfunction "-IN_6") (pintype "input"))
      (node (ref "MCP6004-TRIG") (pin "7") (pinfunction "OUT_7") (pintype "output"))
      (node (ref "TRIG2") (pin "TIP") (pinfunction "TIP_TIP") (pintype "passive"))
    )
    (net (code "41") (name "Net-(MCP6004-TRIGC--IN)") (class "Default")
      (node (ref "MCP6004-TRIG") (pin "8") (pinfunction "OUT_8") (pintype "output"))
      (node (ref "MCP6004-TRIG") (pin "9") (pinfunction "-IN_9") (pintype "input"))
      (node (ref "TRIG1") (pin "TIP") (pinfunction "TIP_TIP") (pintype "passive"))
    )
    (net (code "42") (name "Net-(MCP6004-TRIGD--IN)") (class "Default")
      (node (ref "MCP6004-TRIG") (pin "13") (pinfunction "-IN_13") (pintype "input"))
      (node (ref "MCP6004-TRIG") (pin "14") (pinfunction "OUT_14") (pintype "output"))
      (node (ref "TRIG4") (pin "TIP") (pinfunction "TIP_TIP") (pintype "passive"))
    )
    (net (code "43") (name "Net-(MCP6004-VA--IN)") (class "Default")
      (node (ref "CV3") (pin "TIP") (pinfunction "TIP_TIP") (pintype "passive"))
      (node (ref "MCP6004-V") (pin "1") (pinfunction "OUT_1") (pintype "output"))
      (node (ref "MCP6004-V") (pin "2") (pinfunction "-IN_2") (pintype "input"))
    )
    (net (code "44") (name "Net-(MCP6004-VB--IN)") (class "Default")
      (node (ref "CV4") (pin "TIP") (pinfunction "TIP_TIP") (pintype "passive"))
      (node (ref "MCP6004-V") (pin "6") (pinfunction "-IN_6") (pintype "input"))
      (node (ref "MCP6004-V") (pin "7") (pinfunction "OUT_7") (pintype "output"))
    )
    (net (code "45") (name "Net-(MCP6004-VC--IN)") (class "Default")
      (node (ref "CV1") (pin "TIP") (pinfunction "TIP_TIP") (pintype "passive"))
      (node (ref "MCP6004-V") (pin "8") (pinfunction "OUT_8") (pintype "output"))
      (node (ref "MCP6004-V") (pin "9") (pinfunction "-IN_9") (pintype "input"))
    )
    (net (code "46") (name "Net-(MCP6004-VD--IN)") (class "Default")
      (node (ref "CV2") (pin "TIP") (pinfunction "TIP_TIP") (pintype "passive"))
      (node (ref "MCP6004-V") (pin "13") (pinfunction "-IN_13") (pintype "input"))
      (node (ref "MCP6004-V") (pin "14") (pinfunction "OUT_14") (pintype "output"))
    )
    (net (code "47") (name "Net-(U1-PB6(XTAL1{slash}TOSC1))") (class "Default")
      (node (ref "C17") (pin "1") (pinfunction "1_1") (pintype "passive"))
      (node (ref "Q2") (pin "2") (pinfunction "2_2") (pintype "passive"))
      (node (ref "U1") (pin "7") (pinfunction "PB6(XTAL1/TOSC1)_7") (pintype "bidirectional"))
    )
    (net (code "48") (name "Net-(U1-PB7(XTAL2{slash}TOSC2))") (class "Default")
      (node (ref "C18") (pin "1") (pinfunction "1_1") (pintype "passive"))
      (node (ref "Q2") (pin "1") (pinfunction "1_1") (pintype "passive"))
      (node (ref "U1") (pin "8") (pinfunction "PB7(XTAL2/TOSC2)_8") (pintype "bidirectional"))
    )
    (net (code "49") (name "POT1") (class "Default")
      (node (ref "GLIDE1") (pin "P$2") (pinfunction "2_P$2") (pintype "passive"))
      (node (ref "U1") (pin "19") (pinfunction "ADC6_19") (pintype "bidirectional"))
    )
    (net (code "50") (name "POT2") (class "Default")
      (node (ref "GATE") (pin "P$2") (pinfunction "2_P$2") (pintype "passive"))
      (node (ref "U1") (pin "22") (pinfunction "ADC7_22") (pintype "bidirectional"))
    )
    (net (code "51") (name "RST") (class "Default")
      (node (ref "ISP1") (pin "5") (pinfunction "RST_5") (pintype "output"))
      (node (ref "U1") (pin "29") (pinfunction "PC6(/RESET)_29") (pintype "bidirectional"))
    )
    (net (code "52") (name "SCK") (class "Default")
      (node (ref "ISP1") (pin "3") (pinfunction "SCK_3") (pintype "output"))
      (node (ref "MCP4922") (pin "4") (pinfunction "SCK_4") (pintype "input"))
      (node (ref "MCP4922-2") (pin "4") (pinfunction "SCK_4") (pintype "input"))
      (node (ref "U1") (pin "17") (pinfunction "PB5(SCK)_17") (pintype "bidirectional"))
    )
    (net (code "53") (name "T0") (class "Default")
      (node (ref "74238") (pin "15") (pinfunction "Y0_15") (pintype "output"))
      (node (ref "R18") (pin "2") (pinfunction "2_2") (pintype "passive"))
      (node (ref "U$4") (pin "1") (pinfunction "1_1") (pintype "passive"))
    )
    (net (code "54") (name "T1") (class "Default")
      (node (ref "74238") (pin "14") (pinfunction "Y1_14") (pintype "output"))
      (node (ref "R17") (pin "2") (pinfunction "2_2") (pintype "passive"))
      (node (ref "U$4") (pin "3") (pinfunction "3_3") (pintype "passive"))
    )
    (net (code "55") (name "T2") (class "Default")
      (node (ref "74238") (pin "13") (pinfunction "Y2_13") (pintype "output"))
      (node (ref "R16") (pin "2") (pinfunction "2_2") (pintype "passive"))
      (node (ref "U$4") (pin "5") (pinfunction "5_5") (pintype "passive"))
    )
    (net (code "56") (name "T3") (class "Default")
      (node (ref "74238") (pin "12") (pinfunction "Y3_12") (pintype "output"))
      (node (ref "R15") (pin "2") (pinfunction "2_2") (pintype "passive"))
      (node (ref "U$4") (pin "7") (pinfunction "7_7") (pintype "passive"))
    )
    (net (code "57") (name "T4") (class "Default")
      (node (ref "74238") (pin "11") (pinfunction "Y4_11") (pintype "output"))
      (node (ref "R19") (pin "2") (pinfunction "2_2") (pintype "passive"))
      (node (ref "U$4") (pin "9") (pinfunction "9_9") (pintype "passive"))
    )
    (net (code "58") (name "T5") (class "Default")
      (node (ref "74238") (pin "10") (pinfunction "Y5_10") (pintype "output"))
      (node (ref "R20") (pin "2") (pinfunction "2_2") (pintype "passive"))
      (node (ref "U$4") (pin "11") (pinfunction "11_11") (pintype "passive"))
    )
    (net (code "59") (name "T6") (class "Default")
      (node (ref "74238") (pin "9") (pinfunction "Y6_9") (pintype "output"))
      (node (ref "R21") (pin "2") (pinfunction "2_2") (pintype "passive"))
      (node (ref "U$4") (pin "13") (pinfunction "13_13") (pintype "passive"))
    )
    (net (code "60") (name "T7") (class "Default")
      (node (ref "74238") (pin "7") (pinfunction "Y7_7") (pintype "output"))
      (node (ref "R22") (pin "2") (pinfunction "2_2") (pintype "passive"))
      (node (ref "U$4") (pin "15") (pinfunction "15_15") (pintype "passive"))
    )
    (net (code "61") (name "TRIG1") (class "Default")
      (node (ref "MCP6004-TRIG") (pin "10") (pinfunction "+IN_10") (pintype "input"))
      (node (ref "U1") (pin "28") (pinfunction "PC5(ADC5/SCL)_28") (pintype "bidirectional"))
    )
    (net (code "62") (name "TRIG2") (class "Default")
      (node (ref "MCP6004-TRIG") (pin "5") (pinfunction "+IN_5") (pintype "input"))
      (node (ref "U1") (pin "30") (pinfunction "PD0(RXD)_30") (pintype "bidirectional"))
    )
    (net (code "63") (name "TRIG3") (class "Default")
      (node (ref "MCP6004-TRIG") (pin "3") (pinfunction "+IN_3") (pintype "input"))
      (node (ref "U1") (pin "31") (pinfunction "PD1(TXD)_31") (pintype "bidirectional"))
    )
    (net (code "64") (name "TRIG4") (class "Default")
      (node (ref "MCP6004-TRIG") (pin "12") (pinfunction "+IN_12") (pintype "input"))
      (node (ref "U1") (pin "1") (pinfunction "PD3(INT1)_1") (pintype "bidirectional"))
    )
    (net (code "65") (name "VOUTA") (class "Default")
      (node (ref "MCP4922") (pin "14") (pinfunction "VOUTA_14") (pintype "output"))
      (node (ref "MCP6004-V") (pin "10") (pinfunction "+IN_10") (pintype "input"))
    )
    (net (code "66") (name "VOUTB") (class "Default")
      (node (ref "MCP4922") (pin "10") (pinfunction "VOUTB_10") (pintype "output"))
      (node (ref "MCP6004-V") (pin "12") (pinfunction "+IN_12") (pintype "input"))
    )
    (net (code "67") (name "VOUTC") (class "Default")
      (node (ref "MCP4922-2") (pin "14") (pinfunction "VOUTA_14") (pintype "output"))
      (node (ref "MCP6004-V") (pin "3") (pinfunction "+IN_3") (pintype "input"))
    )
    (net (code "68") (name "VOUTD") (class "Default")
      (node (ref "MCP4922-2") (pin "10") (pinfunction "VOUTB_10") (pintype "output"))
      (node (ref "MCP6004-V") (pin "5") (pinfunction "+IN_5") (pintype "input"))
    )
    (net (code "69") (name "unconnected-(74151-1A-W-Pad6)") (class "Default")
      (node (ref "74151-1") (pin "6") (pinfunction "W_6") (pintype "output"))
    )
    (net (code "70") (name "unconnected-(75151-2A-W-Pad6)") (class "Default")
      (node (ref "75151-2") (pin "6") (pinfunction "W_6") (pintype "output"))
    )
    (net (code "71") (name "unconnected-(CLK_IN-PadNORM)") (class "Default")
      (node (ref "CLK_IN") (pin "NORM") (pinfunction "NORM_NORM") (pintype "passive"))
    )
    (net (code "72") (name "unconnected-(CV1-PadNORM)") (class "Default")
      (node (ref "CV1") (pin "NORM") (pinfunction "NORM_NORM") (pintype "passive"))
    )
    (net (code "73") (name "unconnected-(CV2-PadNORM)") (class "Default")
      (node (ref "CV2") (pin "NORM") (pinfunction "NORM_NORM") (pintype "passive"))
    )
    (net (code "74") (name "unconnected-(CV3-PadNORM)") (class "Default")
      (node (ref "CV3") (pin "NORM") (pinfunction "NORM_NORM") (pintype "passive"))
    )
    (net (code "75") (name "unconnected-(CV4-PadNORM)") (class "Default")
      (node (ref "CV4") (pin "NORM") (pinfunction "NORM_NORM") (pintype "passive"))
    )
    (net (code "76") (name "unconnected-(JP2-PadD+)") (class "Default")
      (node (ref "JP2") (pin "D+") (pinfunction "D+_D+") (pintype "bidirectional"))
    )
    (net (code "77") (name "unconnected-(JP2-PadD-)") (class "Default")
      (node (ref "JP2") (pin "D-") (pinfunction "D-_D-") (pintype "bidirectional"))
    )
    (net (code "78") (name "unconnected-(REF-NC-Pad3)") (class "Default")
      (node (ref "REF") (pin "3") (pinfunction "NC_3") (pintype "no_connect"))
    )
    (net (code "79") (name "unconnected-(TRIG1-PadNORM)") (class "Default")
      (node (ref "TRIG1") (pin "NORM") (pinfunction "NORM_NORM") (pintype "passive"))
    )
    (net (code "80") (name "unconnected-(TRIG2-PadNORM)") (class "Default")
      (node (ref "TRIG2") (pin "NORM") (pinfunction "NORM_NORM") (pintype "passive"))
    )
    (net (code "81") (name "unconnected-(TRIG3-PadNORM)") (class "Default")
      (node (ref "TRIG3") (pin "NORM") (pinfunction "NORM_NORM") (pintype "passive"))
    )
    (net (code "82") (name "unconnected-(TRIG4-PadNORM)") (class "Default")
      (node (ref "TRIG4") (pin "NORM") (pinfunction "NORM_NORM") (pintype "passive"))
    )
    (net (code "83") (name "unconnected-(U$4-Pad17)") (class "Default")
      (node (ref "U$4") (pin "17") (pinfunction "17_17") (pintype "passive"))
    )
    (net (code "84") (name "unconnected-(U$4-Pad19)") (class "Default")
      (node (ref "U$4") (pin "19") (pinfunction "19_19") (pintype "passive"))
    )
    (net (code "85") (name "unconnected-(U1-AREF-Pad20)") (class "Default")
      (node (ref "U1") (pin "20") (pinfunction "AREF_20") (pintype "bidirectional"))
    )
  )
)
